# transmisor.net
KiCad netlist of a schematic drawn in EAGLE
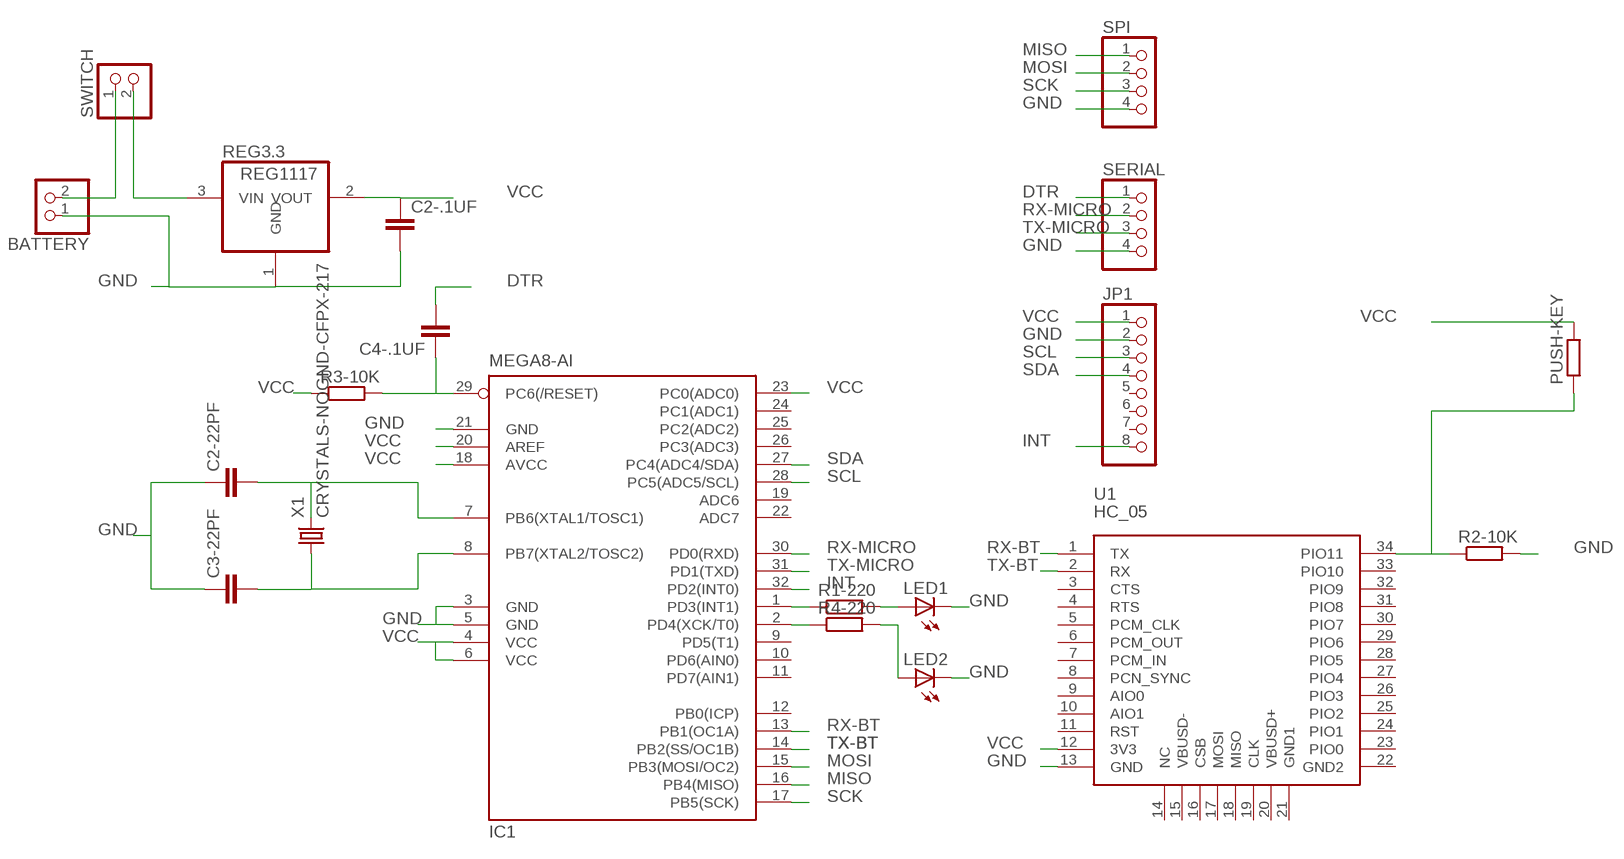
[diagram p0: schematic, sheet 1]

(export (version "E")
  (design (tool "Eeschema 10.0.6"))
  (components
    (comp (ref "BATTERY")
      (value "PINHD-1X2")
      (footprint "eagle-import:1X02")
      (libsource (lib "eagle-import") (part "PINHD-1X2"))
    )
    (comp (ref "C2-.1UF")
      (value "C-EUC0805")
      (footprint "eagle-import:C0805")
      (libsource (lib "eagle-import") (part "C-EUC0805"))
    )
    (comp (ref "C2-22PF")
      (value "C-EUC0805")
      (footprint "eagle-import:C0805")
      (libsource (lib "eagle-import") (part "C-EUC0805"))
    )
    (comp (ref "C3-22PF")
      (value "C-EUC0805")
      (footprint "eagle-import:C0805")
      (libsource (lib "eagle-import") (part "C-EUC0805"))
    )
    (comp (ref "C4-.1UF")
      (value "C-EUC0805")
      (footprint "eagle-import:C0805")
      (libsource (lib "eagle-import") (part "C-EUC0805"))
    )
    (comp (ref "IC1")
      (value "MEGA8-AI")
      (footprint "eagle-import:TQFP32-08")
      (fields (field (name "MPN") "ATMEGA8-16AU"))
      (libsource (lib "eagle-import") (part "MEGA8-AI"))
    )
    (comp (ref "JP1")
      (value "PINHD-1X8")
      (footprint "eagle-import:1X08")
      (libsource (lib "eagle-import") (part "PINHD-1X8"))
    )
    (comp (ref "LED1")
      (value "LEDMINI-TOP")
      (footprint "eagle-import:OSRAM-MINI-TOP-LED")
      (libsource (lib "eagle-import") (part "LEDMINI-TOP"))
    )
    (comp (ref "LED2")
      (value "LEDMINI-TOP")
      (footprint "eagle-import:OSRAM-MINI-TOP-LED")
      (libsource (lib "eagle-import") (part "LEDMINI-TOP"))
    )
    (comp (ref "PUSH-KEY")
      (value "R-EU_M5923")
      (footprint "eagle-import:M5923")
      (libsource (lib "eagle-import") (part "R-EU_M5923"))
    )
    (comp (ref "R1-220")
      (value "R-EU_M0805")
      (footprint "eagle-import:M0805")
      (libsource (lib "eagle-import") (part "resistor_R-EU_M0805"))
    )
    (comp (ref "R2-10K")
      (value "R-EU_M0805")
      (footprint "eagle-import:M0805")
      (libsource (lib "eagle-import") (part "resistor_R-EU_M0805"))
    )
    (comp (ref "R3-10K")
      (value "R-EU_M0805")
      (footprint "eagle-import:M0805")
      (libsource (lib "eagle-import") (part "resistor_R-EU_M0805"))
    )
    (comp (ref "R4-220")
      (value "R-EU_M0805")
      (footprint "eagle-import:M0805")
      (libsource (lib "eagle-import") (part "resistor_R-EU_M0805"))
    )
    (comp (ref "REG3.3")
      (value "REG1117")
      (footprint "eagle-import:SOT223")
      (libsource (lib "eagle-import") (part "REG1117"))
    )
    (comp (ref "SERIAL")
      (value "PINHD-1X4")
      (footprint "eagle-import:1X04")
      (libsource (lib "eagle-import") (part "PINHD-1X4"))
    )
    (comp (ref "SPI")
      (value "PINHD-1X4")
      (footprint "eagle-import:1X04")
      (libsource (lib "eagle-import") (part "PINHD-1X4"))
    )
    (comp (ref "SWITCH")
      (value "PINHD-1X2")
      (footprint "eagle-import:1X02")
      (libsource (lib "eagle-import") (part "PINHD-1X2"))
    )
    (comp (ref "U1")
      (value "HC_05")
      (footprint "eagle-import:BLUETOOTH_SMD")
      (libsource (lib "eagle-import") (part "HC_05"))
    )
    (comp (ref "X1")
      (value "CRYSTALS-NOGND-CFPX-217")
      (footprint "eagle-import:3.2X1.5-2-PAD")
      (libsource (lib "eagle-import") (part "CRYSTALS-NOGND-CFPX-217"))
    )
  )
  (nets
    (net (code "1") (name "/DTR") (class "Default")
      (node (ref "C4-.1UF") (pin "2") (pinfunction "2_2") (pintype "passive"))
      (node (ref "SERIAL") (pin "1") (pinfunction "1_1") (pintype "passive"))
    )
    (net (code "2") (name "/GND") (class "Default")
      (node (ref "BATTERY") (pin "1") (pinfunction "1_1") (pintype "passive"))
      (node (ref "C2-.1UF") (pin "2") (pinfunction "2_2") (pintype "passive"))
      (node (ref "C2-22PF") (pin "1") (pinfunction "1_1") (pintype "passive"))
      (node (ref "C3-22PF") (pin "1") (pinfunction "1_1") (pintype "passive"))
      (node (ref "IC1") (pin "21") (pinfunction "GND_21") (pintype "power_in"))
      (node (ref "IC1") (pin "3") (pinfunction "GND_3") (pintype "power_in"))
      (node (ref "IC1") (pin "5") (pinfunction "GND_5") (pintype "power_in"))
      (node (ref "JP1") (pin "2") (pinfunction "2_2") (pintype "passive"))
      (node (ref "LED1") (pin "C") (pinfunction "C_C") (pintype "passive"))
      (node (ref "LED2") (pin "C") (pinfunction "C_C") (pintype "passive"))
      (node (ref "R2-10K") (pin "2") (pinfunction "2_2") (pintype "passive"))
      (node (ref "REG3.3") (pin "1") (pinfunction "GND_1") (pintype "power_in"))
      (node (ref "SERIAL") (pin "4") (pinfunction "4_4") (pintype "passive"))
      (node (ref "SPI") (pin "4") (pinfunction "4_4") (pintype "passive"))
      (node (ref "U1") (pin "13") (pinfunction "GND_13") (pintype "bidirectional"))
    )
    (net (code "3") (name "/INT") (class "Default")
      (node (ref "IC1") (pin "32") (pinfunction "PD2(INT0)_32") (pintype "bidirectional"))
      (node (ref "JP1") (pin "8") (pinfunction "8_8") (pintype "passive"))
    )
    (net (code "4") (name "/MISO") (class "Default")
      (node (ref "IC1") (pin "16") (pinfunction "PB4(MISO)_16") (pintype "bidirectional"))
      (node (ref "SPI") (pin "1") (pinfunction "1_1") (pintype "passive"))
    )
    (net (code "5") (name "/MOSI") (class "Default")
      (node (ref "IC1") (pin "15") (pinfunction "PB3(MOSI/OC2)_15") (pintype "bidirectional"))
      (node (ref "SPI") (pin "2") (pinfunction "2_2") (pintype "passive"))
    )
    (net (code "6") (name "/RX-BT") (class "Default")
      (node (ref "IC1") (pin "13") (pinfunction "PB1(OC1A)_13") (pintype "bidirectional"))
      (node (ref "U1") (pin "1") (pinfunction "TX_1") (pintype "bidirectional"))
    )
    (net (code "7") (name "/RX-MICRO") (class "Default")
      (node (ref "IC1") (pin "30") (pinfunction "PD0(RXD)_30") (pintype "bidirectional"))
      (node (ref "SERIAL") (pin "2") (pinfunction "2_2") (pintype "passive"))
    )
    (net (code "8") (name "/SCK") (class "Default")
      (node (ref "IC1") (pin "17") (pinfunction "PB5(SCK)_17") (pintype "bidirectional"))
      (node (ref "SPI") (pin "3") (pinfunction "3_3") (pintype "passive"))
    )
    (net (code "9") (name "/SCL") (class "Default")
      (node (ref "IC1") (pin "28") (pinfunction "PC5(ADC5/SCL)_28") (pintype "bidirectional"))
      (node (ref "JP1") (pin "3") (pinfunction "3_3") (pintype "passive"))
    )
    (net (code "10") (name "/SDA") (class "Default")
      (node (ref "IC1") (pin "27") (pinfunction "PC4(ADC4/SDA)_27") (pintype "bidirectional"))
      (node (ref "JP1") (pin "4") (pinfunction "4_4") (pintype "passive"))
    )
    (net (code "11") (name "/TX-BT") (class "Default")
      (node (ref "IC1") (pin "14") (pinfunction "PB2(SS/OC1B)_14") (pintype "bidirectional"))
      (node (ref "U1") (pin "2") (pinfunction "RX_2") (pintype "bidirectional"))
    )
    (net (code "12") (name "/TX-MICRO") (class "Default")
      (node (ref "IC1") (pin "31") (pinfunction "PD1(TXD)_31") (pintype "bidirectional"))
      (node (ref "SERIAL") (pin "3") (pinfunction "3_3") (pintype "passive"))
    )
    (net (code "13") (name "/VCC") (class "Default")
      (node (ref "C2-.1UF") (pin "1") (pinfunction "1_1") (pintype "passive"))
      (node (ref "IC1") (pin "18") (pinfunction "AVCC_18") (pintype "power_in"))
      (node (ref "IC1") (pin "20") (pinfunction "AREF_20") (pintype "passive"))
      (node (ref "IC1") (pin "23") (pinfunction "PC0(ADC0)_23") (pintype "bidirectional"))
      (node (ref "IC1") (pin "4") (pinfunction "VCC_4") (pintype "power_in"))
      (node (ref "IC1") (pin "6") (pinfunction "VCC_6") (pintype "power_in"))
      (node (ref "JP1") (pin "1") (pinfunction "1_1") (pintype "passive"))
      (node (ref "PUSH-KEY") (pin "2") (pinfunction "2_2") (pintype "passive"))
      (node (ref "R3-10K") (pin "1") (pinfunction "1_1") (pintype "passive"))
      (node (ref "REG3.3") (pin "2") (pinfunction "VOUT_2") (pintype "output"))
      (node (ref "U1") (pin "12") (pinfunction "3V3_12") (pintype "bidirectional"))
    )
    (net (code "14") (name "Net-(BATTERY-Pad2)") (class "Default")
      (node (ref "BATTERY") (pin "2") (pinfunction "2_2") (pintype "passive"))
      (node (ref "SWITCH") (pin "1") (pinfunction "1_1") (pintype "passive"))
    )
    (net (code "15") (name "Net-(IC1-PB6(XTAL1{slash}TOSC1))") (class "Default")
      (node (ref "C2-22PF") (pin "2") (pinfunction "2_2") (pintype "passive"))
      (node (ref "IC1") (pin "7") (pinfunction "PB6(XTAL1/TOSC1)_7") (pintype "bidirectional"))
      (node (ref "X1") (pin "2") (pinfunction "2_2") (pintype "passive"))
    )
    (net (code "16") (name "Net-(IC1-PB7(XTAL2{slash}TOSC2))") (class "Default")
      (node (ref "C3-22PF") (pin "2") (pinfunction "2_2") (pintype "passive"))
      (node (ref "IC1") (pin "8") (pinfunction "PB7(XTAL2/TOSC2)_8") (pintype "bidirectional"))
      (node (ref "X1") (pin "1") (pinfunction "1_1") (pintype "passive"))
    )
    (net (code "17") (name "Net-(IC1-PC6({slash}RESET))") (class "Default")
      (node (ref "C4-.1UF") (pin "1") (pinfunction "1_1") (pintype "passive"))
      (node (ref "IC1") (pin "29") (pinfunction "PC6(/RESET)_29") (pintype "bidirectional"))
      (node (ref "R3-10K") (pin "2") (pinfunction "2_2") (pintype "passive"))
    )
    (net (code "18") (name "Net-(IC1-PD3(INT1))") (class "Default")
      (node (ref "IC1") (pin "1") (pinfunction "PD3(INT1)_1") (pintype "bidirectional"))
      (node (ref "R1-220") (pin "1") (pinfunction "1_1") (pintype "passive"))
    )
    (net (code "19") (name "Net-(IC1-PD4(XCK{slash}T0))") (class "Default")
      (node (ref "IC1") (pin "2") (pinfunction "PD4(XCK/T0)_2") (pintype "bidirectional"))
      (node (ref "R4-220") (pin "1") (pinfunction "1_1") (pintype "passive"))
    )
    (net (code "20") (name "Net-(LED1-PadA)") (class "Default")
      (node (ref "LED1") (pin "A") (pinfunction "A_A") (pintype "passive"))
      (node (ref "R1-220") (pin "2") (pinfunction "2_2") (pintype "passive"))
    )
    (net (code "21") (name "Net-(LED2-PadA)") (class "Default")
      (node (ref "LED2") (pin "A") (pinfunction "A_A") (pintype "passive"))
      (node (ref "R4-220") (pin "2") (pinfunction "2_2") (pintype "passive"))
    )
    (net (code "22") (name "Net-(REG3.3-VIN)") (class "Default")
      (node (ref "REG3.3") (pin "3") (pinfunction "VIN_3") (pintype "input"))
      (node (ref "SWITCH") (pin "2") (pinfunction "2_2") (pintype "passive"))
    )
    (net (code "23") (name "Net-(U1-PIO11)") (class "Default")
      (node (ref "PUSH-KEY") (pin "1") (pinfunction "1_1") (pintype "passive"))
      (node (ref "R2-10K") (pin "1") (pinfunction "1_1") (pintype "passive"))
      (node (ref "U1") (pin "34") (pinfunction "PIO11_34") (pintype "bidirectional"))
    )
    (net (code "24") (name "unconnected-(IC1-ADC6-Pad19)") (class "Default")
      (node (ref "IC1") (pin "19") (pinfunction "ADC6_19") (pintype "bidirectional"))
    )
    (net (code "25") (name "unconnected-(IC1-ADC7-Pad22)") (class "Default")
      (node (ref "IC1") (pin "22") (pinfunction "ADC7_22") (pintype "bidirectional"))
    )
    (net (code "26") (name "unconnected-(IC1-PB0(ICP)-Pad12)") (class "Default")
      (node (ref "IC1") (pin "12") (pinfunction "PB0(ICP)_12") (pintype "bidirectional"))
    )
    (net (code "27") (name "unconnected-(IC1-PC1(ADC1)-Pad24)") (class "Default")
      (node (ref "IC1") (pin "24") (pinfunction "PC1(ADC1)_24") (pintype "bidirectional"))
    )
    (net (code "28") (name "unconnected-(IC1-PC2(ADC2)-Pad25)") (class "Default")
      (node (ref "IC1") (pin "25") (pinfunction "PC2(ADC2)_25") (pintype "bidirectional"))
    )
    (net (code "29") (name "unconnected-(IC1-PC3(ADC3)-Pad26)") (class "Default")
      (node (ref "IC1") (pin "26") (pinfunction "PC3(ADC3)_26") (pintype "bidirectional"))
    )
    (net (code "30") (name "unconnected-(IC1-PD5(T1)-Pad9)") (class "Default")
      (node (ref "IC1") (pin "9") (pinfunction "PD5(T1)_9") (pintype "bidirectional"))
    )
    (net (code "31") (name "unconnected-(IC1-PD6(AIN0)-Pad10)") (class "Default")
      (node (ref "IC1") (pin "10") (pinfunction "PD6(AIN0)_10") (pintype "bidirectional"))
    )
    (net (code "32") (name "unconnected-(IC1-PD7(AIN1)-Pad11)") (class "Default")
      (node (ref "IC1") (pin "11") (pinfunction "PD7(AIN1)_11") (pintype "bidirectional"))
    )
    (net (code "33") (name "unconnected-(JP1-Pad5)") (class "Default")
      (node (ref "JP1") (pin "5") (pinfunction "5_5") (pintype "passive"))
    )
    (net (code "34") (name "unconnected-(JP1-Pad6)") (class "Default")
      (node (ref "JP1") (pin "6") (pinfunction "6_6") (pintype "passive"))
    )
    (net (code "35") (name "unconnected-(JP1-Pad7)") (class "Default")
      (node (ref "JP1") (pin "7") (pinfunction "7_7") (pintype "passive"))
    )
    (net (code "36") (name "unconnected-(U1-AIO0-Pad9)") (class "Default")
      (node (ref "U1") (pin "9") (pinfunction "AIO0_9") (pintype "bidirectional"))
    )
    (net (code "37") (name "unconnected-(U1-AIO1-Pad10)") (class "Default")
      (node (ref "U1") (pin "10") (pinfunction "AIO1_10") (pintype "bidirectional"))
    )
    (net (code "38") (name "unconnected-(U1-CLK-Pad19)") (class "Default")
      (node (ref "U1") (pin "19") (pinfunction "CLK_19") (pintype "bidirectional"))
    )
    (net (code "39") (name "unconnected-(U1-CSB-Pad16)") (class "Default")
      (node (ref "U1") (pin "16") (pinfunction "CSB_16") (pintype "bidirectional"))
    )
    (net (code "40") (name "unconnected-(U1-CTS-Pad3)") (class "Default")
      (node (ref "U1") (pin "3") (pinfunction "CTS_3") (pintype "bidirectional"))
    )
    (net (code "41") (name "unconnected-(U1-GND1-Pad21)") (class "Default")
      (node (ref "U1") (pin "21") (pinfunction "GND1_21") (pintype "bidirectional"))
    )
    (net (code "42") (name "unconnected-(U1-GND2-Pad22)") (class "Default")
      (node (ref "U1") (pin "22") (pinfunction "GND2_22") (pintype "bidirectional"))
    )
    (net (code "43") (name "unconnected-(U1-MISO-Pad18)") (class "Default")
      (node (ref "U1") (pin "18") (pinfunction "MISO_18") (pintype "bidirectional"))
    )
    (net (code "44") (name "unconnected-(U1-MOSI-Pad17)") (class "Default")
      (node (ref "U1") (pin "17") (pinfunction "MOSI_17") (pintype "bidirectional"))
    )
    (net (code "45") (name "unconnected-(U1-NC-Pad14)") (class "Default")
      (node (ref "U1") (pin "14") (pinfunction "NC_14") (pintype "bidirectional"))
    )
    (net (code "46") (name "unconnected-(U1-PCM_CLK-Pad5)") (class "Default")
      (node (ref "U1") (pin "5") (pinfunction "PCM_CLK_5") (pintype "bidirectional"))
    )
    (net (code "47") (name "unconnected-(U1-PCM_IN-Pad7)") (class "Default")
      (node (ref "U1") (pin "7") (pinfunction "PCM_IN_7") (pintype "bidirectional"))
    )
    (net (code "48") (name "unconnected-(U1-PCM_OUT-Pad6)") (class "Default")
      (node (ref "U1") (pin "6") (pinfunction "PCM_OUT_6") (pintype "bidirectional"))
    )
    (net (code "49") (name "unconnected-(U1-PCN_SYNC-Pad8)") (class "Default")
      (node (ref "U1") (pin "8") (pinfunction "PCN_SYNC_8") (pintype "bidirectional"))
    )
    (net (code "50") (name "unconnected-(U1-PIO0-Pad23)") (class "Default")
      (node (ref "U1") (pin "23") (pinfunction "PIO0_23") (pintype "bidirectional"))
    )
    (net (code "51") (name "unconnected-(U1-PIO1-Pad24)") (class "Default")
      (node (ref "U1") (pin "24") (pinfunction "PIO1_24") (pintype "bidirectional"))
    )
    (net (code "52") (name "unconnected-(U1-PIO2-Pad25)") (class "Default")
      (node (ref "U1") (pin "25") (pinfunction "PIO2_25") (pintype "bidirectional"))
    )
    (net (code "53") (name "unconnected-(U1-PIO3-Pad26)") (class "Default")
      (node (ref "U1") (pin "26") (pinfunction "PIO3_26") (pintype "bidirectional"))
    )
    (net (code "54") (name "unconnected-(U1-PIO4-Pad27)") (class "Default")
      (node (ref "U1") (pin "27") (pinfunction "PIO4_27") (pintype "bidirectional"))
    )
    (net (code "55") (name "unconnected-(U1-PIO5-Pad28)") (class "Default")
      (node (ref "U1") (pin "28") (pinfunction "PIO5_28") (pintype "bidirectional"))
    )
    (net (code "56") (name "unconnected-(U1-PIO6-Pad29)") (class "Default")
      (node (ref "U1") (pin "29") (pinfunction "PIO6_29") (pintype "bidirectional"))
    )
    (net (code "57") (name "unconnected-(U1-PIO7-Pad30)") (class "Default")
      (node (ref "U1") (pin "30") (pinfunction "PIO7_30") (pintype "bidirectional"))
    )
    (net (code "58") (name "unconnected-(U1-PIO8-Pad31)") (class "Default")
      (node (ref "U1") (pin "31") (pinfunction "PIO8_31") (pintype "bidirectional"))
    )
    (net (code "59") (name "unconnected-(U1-PIO9-Pad32)") (class "Default")
      (node (ref "U1") (pin "32") (pinfunction "PIO9_32") (pintype "bidirectional"))
    )
    (net (code "60") (name "unconnected-(U1-PIO10-Pad33)") (class "Default")
      (node (ref "U1") (pin "33") (pinfunction "PIO10_33") (pintype "bidirectional"))
    )
    (net (code "61") (name "unconnected-(U1-RST-Pad11)") (class "Default")
      (node (ref "U1") (pin "11") (pinfunction "RST_11") (pintype "bidirectional"))
    )
    (net (code "62") (name "unconnected-(U1-RTS-Pad4)") (class "Default")
      (node (ref "U1") (pin "4") (pinfunction "RTS_4") (pintype "bidirectional"))
    )
    (net (code "63") (name "unconnected-(U1-VBUSD+-Pad20)") (class "Default")
      (node (ref "U1") (pin "20") (pinfunction "VBUSD+_20") (pintype "bidirectional"))
    )
    (net (code "64") (name "unconnected-(U1-VBUSD--Pad15)") (class "Default")
      (node (ref "U1") (pin "15") (pinfunction "VBUSD-_15") (pintype "bidirectional"))
    )
  )
)
